# PICKIT4-adaptor-SWDOnly.net
KiCad netlist of a schematic drawn in EAGLE
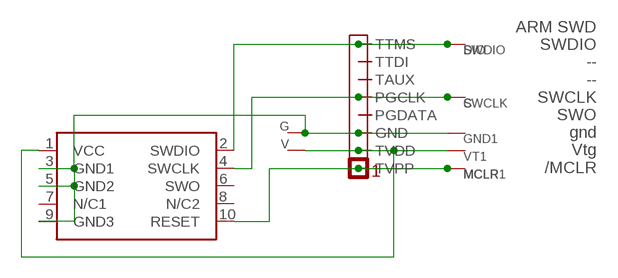
[diagram p0: schematic, sheet 1]

(export (version "E")
  (design (tool "Eeschema 10.0.6"))
  (components
    (comp (ref "C")
      (value "WIRE-R12")
      (footprint "eagle-import:VIA12")
      (libsource (lib "eagle-import") (part "WIRE-R12"))
    )
    (comp (ref "DIO")
      (value "WIRE-R12")
      (footprint "eagle-import:VIA12")
      (libsource (lib "eagle-import") (part "WIRE-R12"))
    )
    (comp (ref "G")
      (value "WIRE-R12")
      (footprint "eagle-import:VIA12")
      (libsource (lib "eagle-import") (part "WIRE-R12"))
    )
    (comp (ref "GND1")
      (value "WIRE-R12")
      (footprint "eagle-import:VIA12")
      (libsource (lib "eagle-import") (part "WIRE-R12"))
    )
    (comp (ref "MCLR")
      (value "WIRE-R12")
      (footprint "eagle-import:VIA12")
      (libsource (lib "eagle-import") (part "WIRE-R12"))
    )
    (comp (ref "MCLR1")
      (value "WIRE-R12")
      (footprint "eagle-import:VIA12")
      (libsource (lib "eagle-import") (part "WIRE-R12"))
    )
    (comp (ref "SWCLK")
      (value "WIRE-R12")
      (footprint "eagle-import:VIA12")
      (libsource (lib "eagle-import") (part "WIRE-R12"))
    )
    (comp (ref "SWD1")
      (value "CORTEX_SWD")
      (footprint "eagle-import:M50-3600542")
      (libsource (lib "eagle-import") (part "CORTEX_SWD"))
    )
    (comp (ref "SWDIO")
      (value "WIRE-R12")
      (footprint "eagle-import:VIA12")
      (libsource (lib "eagle-import") (part "WIRE-R12"))
    )
    (comp (ref "U$1")
      (value "PICKIT4PINHDR")
      (footprint "eagle-import:PINHEAD1X8")
      (libsource (lib "eagle-import") (part "PICKIT4PINHDR"))
    )
    (comp (ref "V")
      (value "WIRE-R12")
      (footprint "eagle-import:VIA12")
      (libsource (lib "eagle-import") (part "WIRE-R12"))
    )
    (comp (ref "VT1")
      (value "WIRE-R12")
      (footprint "eagle-import:VIA12")
      (libsource (lib "eagle-import") (part "WIRE-R12"))
    )
  )
  (nets
    (net (code "1") (name "Net-(SWD1-GND1)") (class "Default")
      (node (ref "G") (pin "P$1") (pinfunction "P$1_P$1") (pintype "bidirectional"))
      (node (ref "GND1") (pin "P$1") (pinfunction "P$1_P$1") (pintype "bidirectional"))
      (node (ref "SWD1") (pin "3") (pinfunction "GND1_3") (pintype "bidirectional"))
      (node (ref "SWD1") (pin "5") (pinfunction "GND2_5") (pintype "bidirectional"))
      (node (ref "SWD1") (pin "9") (pinfunction "GND3_9") (pintype "bidirectional"))
      (node (ref "U$1") (pin "P$3") (pinfunction "GND_P$3") (pintype "power_in"))
    )
    (net (code "2") (name "Net-(SWD1-RESET)") (class "Default")
      (node (ref "MCLR") (pin "P$1") (pinfunction "P$1_P$1") (pintype "bidirectional"))
      (node (ref "MCLR1") (pin "P$1") (pinfunction "P$1_P$1") (pintype "bidirectional"))
      (node (ref "SWD1") (pin "10") (pinfunction "RESET_10") (pintype "bidirectional"))
      (node (ref "U$1") (pin "P$1") (pinfunction "TVPP_P$1") (pintype "bidirectional"))
    )
    (net (code "3") (name "Net-(SWD1-SWCLK)") (class "Default")
      (node (ref "C") (pin "P$1") (pinfunction "P$1_P$1") (pintype "bidirectional"))
      (node (ref "SWCLK") (pin "P$1") (pinfunction "P$1_P$1") (pintype "bidirectional"))
      (node (ref "SWD1") (pin "4") (pinfunction "SWCLK_4") (pintype "bidirectional"))
      (node (ref "U$1") (pin "P$5") (pinfunction "PGCLK_P$5") (pintype "bidirectional"))
    )
    (net (code "4") (name "Net-(SWD1-SWDIO)") (class "Default")
      (node (ref "DIO") (pin "P$1") (pinfunction "P$1_P$1") (pintype "bidirectional"))
      (node (ref "SWD1") (pin "2") (pinfunction "SWDIO_2") (pintype "bidirectional"))
      (node (ref "SWDIO") (pin "P$1") (pinfunction "P$1_P$1") (pintype "bidirectional"))
      (node (ref "U$1") (pin "P$8") (pinfunction "TTMS_P$8") (pintype "bidirectional"))
    )
    (net (code "5") (name "Net-(SWD1-VCC)") (class "Default")
      (node (ref "SWD1") (pin "1") (pinfunction "VCC_1") (pintype "bidirectional"))
      (node (ref "U$1") (pin "P$2") (pinfunction "TVDD_P$2") (pintype "bidirectional"))
      (node (ref "V") (pin "P$1") (pinfunction "P$1_P$1") (pintype "bidirectional"))
      (node (ref "VT1") (pin "P$1") (pinfunction "P$1_P$1") (pintype "bidirectional"))
    )
    (net (code "6") (name "unconnected-(SWD1-N{slash}C1-Pad7)") (class "Default")
      (node (ref "SWD1") (pin "7") (pinfunction "N/C1_7") (pintype "bidirectional"))
    )
    (net (code "7") (name "unconnected-(SWD1-N{slash}C2-Pad8)") (class "Default")
      (node (ref "SWD1") (pin "8") (pinfunction "N/C2_8") (pintype "bidirectional"))
    )
    (net (code "8") (name "unconnected-(SWD1-SWO-Pad6)") (class "Default")
      (node (ref "SWD1") (pin "6") (pinfunction "SWO_6") (pintype "bidirectional"))
    )
    (net (code "9") (name "unconnected-(U$1A-PGDATA-PadP$4)") (class "Default")
      (node (ref "U$1") (pin "P$4") (pinfunction "PGDATA_P$4") (pintype "bidirectional"))
    )
    (net (code "10") (name "unconnected-(U$1A-TAUX-PadP$6)") (class "Default")
      (node (ref "U$1") (pin "P$6") (pinfunction "TAUX_P$6") (pintype "bidirectional"))
    )
    (net (code "11") (name "unconnected-(U$1A-TTDI-PadP$7)") (class "Default")
      (node (ref "U$1") (pin "P$7") (pinfunction "TTDI_P$7") (pintype "bidirectional"))
    )
  )
)
